# Esquem_tico_SensorTemperatura.net
KiCad netlist of a schematic drawn in Altium Designer
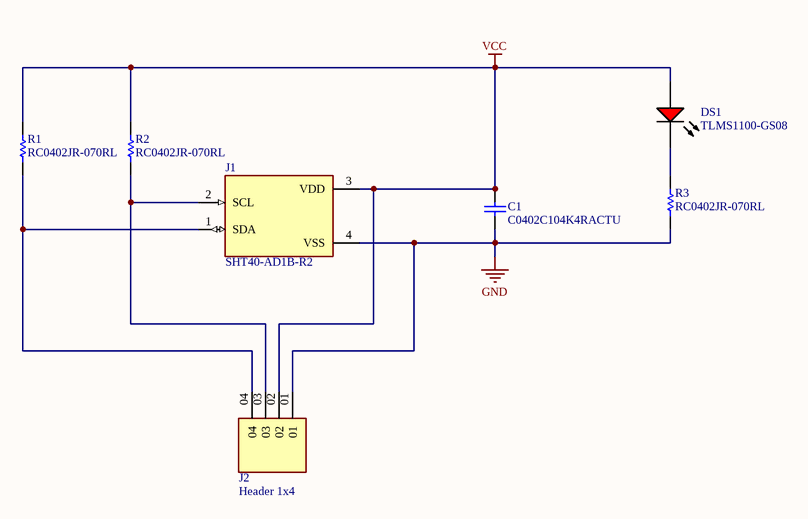
[diagram p0: Esquemático SensorTemperatura.SchDoc]

(export (version "E")
  (design (tool "Eeschema 10.0.6"))
  (components
    (comp (ref "C1")
      (value "C0402C104K4RACTU")
      (footprint "Capacitor")
      (fields (field (name "MANUFACTURER") "Kemet"))
      (libsource (lib "Librería Esquematicos") (part "Capacitor"))
    )
    (comp (ref "DS1")
      (value "TLMS1100-GS08")
      (footprint "LED 0603")
      (description "LED, RED, 2.1 V, -40 to 100 degC, 2-Pin SMD (0603), RoHS, Tape and Reel")
      (fields (field (name "TOLERANCE") "5%"))
      (libsource (lib "Librería Esquematicos") (part "LED 0603"))
    )
    (comp (ref "J1")
      (value "SHT40-AD1B-R2")
      (footprint "SHT40")
      (description "Humidity/Temperature Sensor Digital Serial (I2C) 4-Pin DFN EP T/R")
      (fields (field (name "MF") "Sensirion AG"))
      (libsource (lib "Librería Esquematicos") (part "SHT40-AD1B-R2"))
    )
    (comp (ref "J2")
      (value "Header 1x4")
      (footprint "Header 1x4")
      (fields (field (name "MP") "altium_native_batch"))
      (libsource (lib "Librería Esquematicos") (part "Header 1x4"))
    )
    (comp (ref "R1")
      (value "RC0402JR-070RL")
      (footprint "Resistor")
      (fields (field (name "MANUFACTURER") "Yageo / Phycomp"))
      (libsource (lib "Librería Esquematicos") (part "Resistor"))
    )
    (comp (ref "R2")
      (value "RC0402JR-070RL")
      (footprint "Resistor")
      (fields (field (name "MANUFACTURER") "Yageo / Phycomp"))
      (libsource (lib "Librería Esquematicos") (part "Resistor"))
    )
    (comp (ref "R3")
      (value "RC0402JR-070RL")
      (footprint "Resistor")
      (fields (field (name "MANUFACTURER") "Yageo / Phycomp"))
      (libsource (lib "Librería Esquematicos") (part "Resistor"))
    )
  )
  (nets
    (net (code "1") (name "GND") (class "Default")
      (node (ref "C1") (pin "1") (pinfunction "1_1") (pintype "passive"))
      (node (ref "J1") (pin "4") (pinfunction "VSS_4") (pintype "power_in"))
      (node (ref "J2") (pin "01") (pinfunction "01_01") (pintype "passive"))
      (node (ref "R3") (pin "1") (pinfunction "1_1") (pintype "passive"))
    )
    (net (code "2") (name "Net-(DS1-K)") (class "Default")
      (node (ref "DS1") (pin "2") (pinfunction "K_2") (pintype "passive"))
      (node (ref "R3") (pin "2") (pinfunction "2_2") (pintype "passive"))
    )
    (net (code "3") (name "Net-(J1-SCL)") (class "Default")
      (node (ref "J1") (pin "2") (pinfunction "SCL_2") (pintype "input"))
      (node (ref "J2") (pin "03") (pinfunction "03_03") (pintype "passive"))
      (node (ref "R2") (pin "1") (pinfunction "1_1") (pintype "passive"))
    )
    (net (code "4") (name "Net-(J1-SDA)") (class "Default")
      (node (ref "J1") (pin "1") (pinfunction "SDA_1") (pintype "bidirectional"))
      (node (ref "J2") (pin "04") (pinfunction "04_04") (pintype "passive"))
      (node (ref "R1") (pin "1") (pinfunction "1_1") (pintype "passive"))
    )
    (net (code "5") (name "VCC") (class "Default")
      (node (ref "C1") (pin "2") (pinfunction "2_2") (pintype "passive"))
      (node (ref "DS1") (pin "1") (pinfunction "A_1") (pintype "passive"))
      (node (ref "J1") (pin "3") (pinfunction "VDD_3") (pintype "power_in"))
      (node (ref "J2") (pin "02") (pinfunction "02_02") (pintype "passive"))
      (node (ref "R1") (pin "2") (pinfunction "2_2") (pintype "passive"))
      (node (ref "R2") (pin "2") (pinfunction "2_2") (pintype "passive"))
    )
  )
)
